# Sheet1.net
KiCad netlist of a schematic drawn in Altium Designer
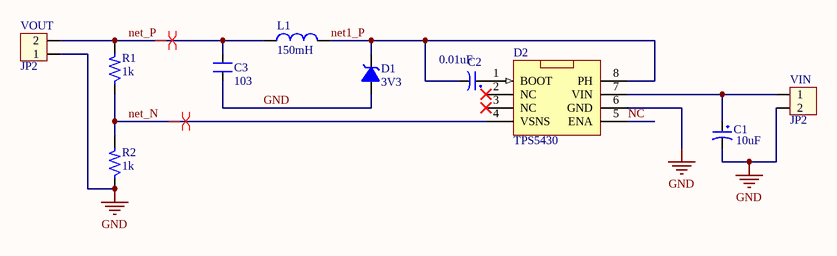
[diagram p0: Sheet1.SchDoc]

(export (version "E")
  (design (tool "Eeschema 10.0.6"))
  (components
    (comp (ref "C1")
      (value "10uF")
      (footprint "CP1/2.5_SM")
      (description "Cap 10000uF/63V")
      (libsource (lib "syhaunguyen") (part "CP9"))
    )
    (comp (ref "C2")
      (value "0.01uF")
      (footprint "CP1/470uF")
      (description "Cap 10000uF/63V")
      (libsource (lib "") (part "CP9_1"))
    )
    (comp (ref "C3")
      (value "103")
      (footprint "SM-0805")
      (description "Cap SMD")
      (libsource (lib "syhaunguyen") (part "CM"))
    )
    (comp (ref "D1")
      (value "3V3")
      (footprint "SM-DIODE")
      (description "Diode Zenner")
      (libsource (lib "syhaunguyen") (part "DZ"))
    )
    (comp (ref "D2")
      (value "TPS5430")
      (footprint "TPS5430")
      (libsource (lib "ChuTrongKhanh") (part "TPS5430"))
    )
    (comp (ref "L1")
      (value "150mH")
      (footprint "L01")
      (description "Inductor")
      (libsource (lib "syhaunguyen") (part "L1"))
    )
    (comp (ref "R1")
      (value "1k")
      (footprint "SM-0805")
      (description "Resistor 1/4W")
      (libsource (lib "syhaunguyen") (part "R"))
    )
    (comp (ref "R2")
      (value "1k")
      (footprint "SM-0805")
      (description "Resistor 1/4W")
      (libsource (lib "syhaunguyen") (part "R"))
    )
    (comp (ref "VIN")
      (value "JP2")
      (footprint "CON2")
      (description "Connector 2")
      (libsource (lib "syhaunguyen") (part "Con2"))
    )
    (comp (ref "VOUT")
      (value "JP2")
      (footprint "CON2")
      (description "Connector 2")
      (libsource (lib "") (part "Con2_1"))
    )
  )
  (nets
    (net (code "1") (name "/NC") (class "Default")
      (node (ref "D2") (pin "5") (pinfunction "ENA_5") (pintype "passive"))
    )
    (net (code "2") (name "/net1_P") (class "Default")
      (node (ref "C2") (pin "2") (pinfunction "2_2") (pintype "passive"))
      (node (ref "D1") (pin "2") (pinfunction "K_2") (pintype "passive"))
      (node (ref "D2") (pin "8") (pinfunction "PH_8") (pintype "passive"))
      (node (ref "L1") (pin "2") (pinfunction "2_2") (pintype "passive"))
    )
    (net (code "3") (name "/net_N") (class "Default")
      (node (ref "D2") (pin "4") (pinfunction "VSNS_4") (pintype "passive"))
      (node (ref "R1") (pin "1") (pinfunction "1_1") (pintype "passive"))
      (node (ref "R2") (pin "2") (pinfunction "2_2") (pintype "passive"))
    )
    (net (code "4") (name "/net_P") (class "Default")
      (node (ref "C3") (pin "2") (pinfunction "2_2") (pintype "passive"))
      (node (ref "L1") (pin "1") (pinfunction "1_1") (pintype "passive"))
      (node (ref "R1") (pin "2") (pinfunction "2_2") (pintype "passive"))
      (node (ref "VOUT") (pin "2") (pinfunction "2_2") (pintype "passive"))
    )
    (net (code "5") (name "GND") (class "Default")
      (node (ref "C1") (pin "2") (pinfunction "2_2") (pintype "passive"))
      (node (ref "C3") (pin "1") (pinfunction "1_1") (pintype "passive"))
      (node (ref "D1") (pin "1") (pinfunction "A_1") (pintype "passive"))
      (node (ref "D2") (pin "6") (pinfunction "GND_6") (pintype "power_in"))
      (node (ref "R2") (pin "1") (pinfunction "1_1") (pintype "passive"))
      (node (ref "VIN") (pin "2") (pinfunction "2_2") (pintype "passive"))
      (node (ref "VOUT") (pin "1") (pinfunction "1_1") (pintype "passive"))
    )
    (net (code "6") (name "Net-(D2-BOOT)") (class "Default")
      (node (ref "C2") (pin "1") (pinfunction "1_1") (pintype "passive"))
      (node (ref "D2") (pin "1") (pinfunction "BOOT_1") (pintype "input"))
    )
    (net (code "7") (name "Net-(D2-VIN)") (class "Default")
      (node (ref "C1") (pin "1") (pinfunction "1_1") (pintype "passive"))
      (node (ref "D2") (pin "7") (pinfunction "VIN_7") (pintype "power_in"))
      (node (ref "VIN") (pin "1") (pinfunction "1_1") (pintype "passive"))
    )
    (net (code "8") (name "unconnected-(D2-NC-Pad2)") (class "Default")
      (node (ref "D2") (pin "2") (pinfunction "NC_2") (pintype "passive+no_connect"))
    )
    (net (code "9") (name "unconnected-(D2-NC-Pad3)") (class "Default")
      (node (ref "D2") (pin "3") (pinfunction "NC_3") (pintype "passive+no_connect"))
    )
  )
)
